# 09_eMMC.net
KiCad netlist of a schematic drawn in Altium Designer
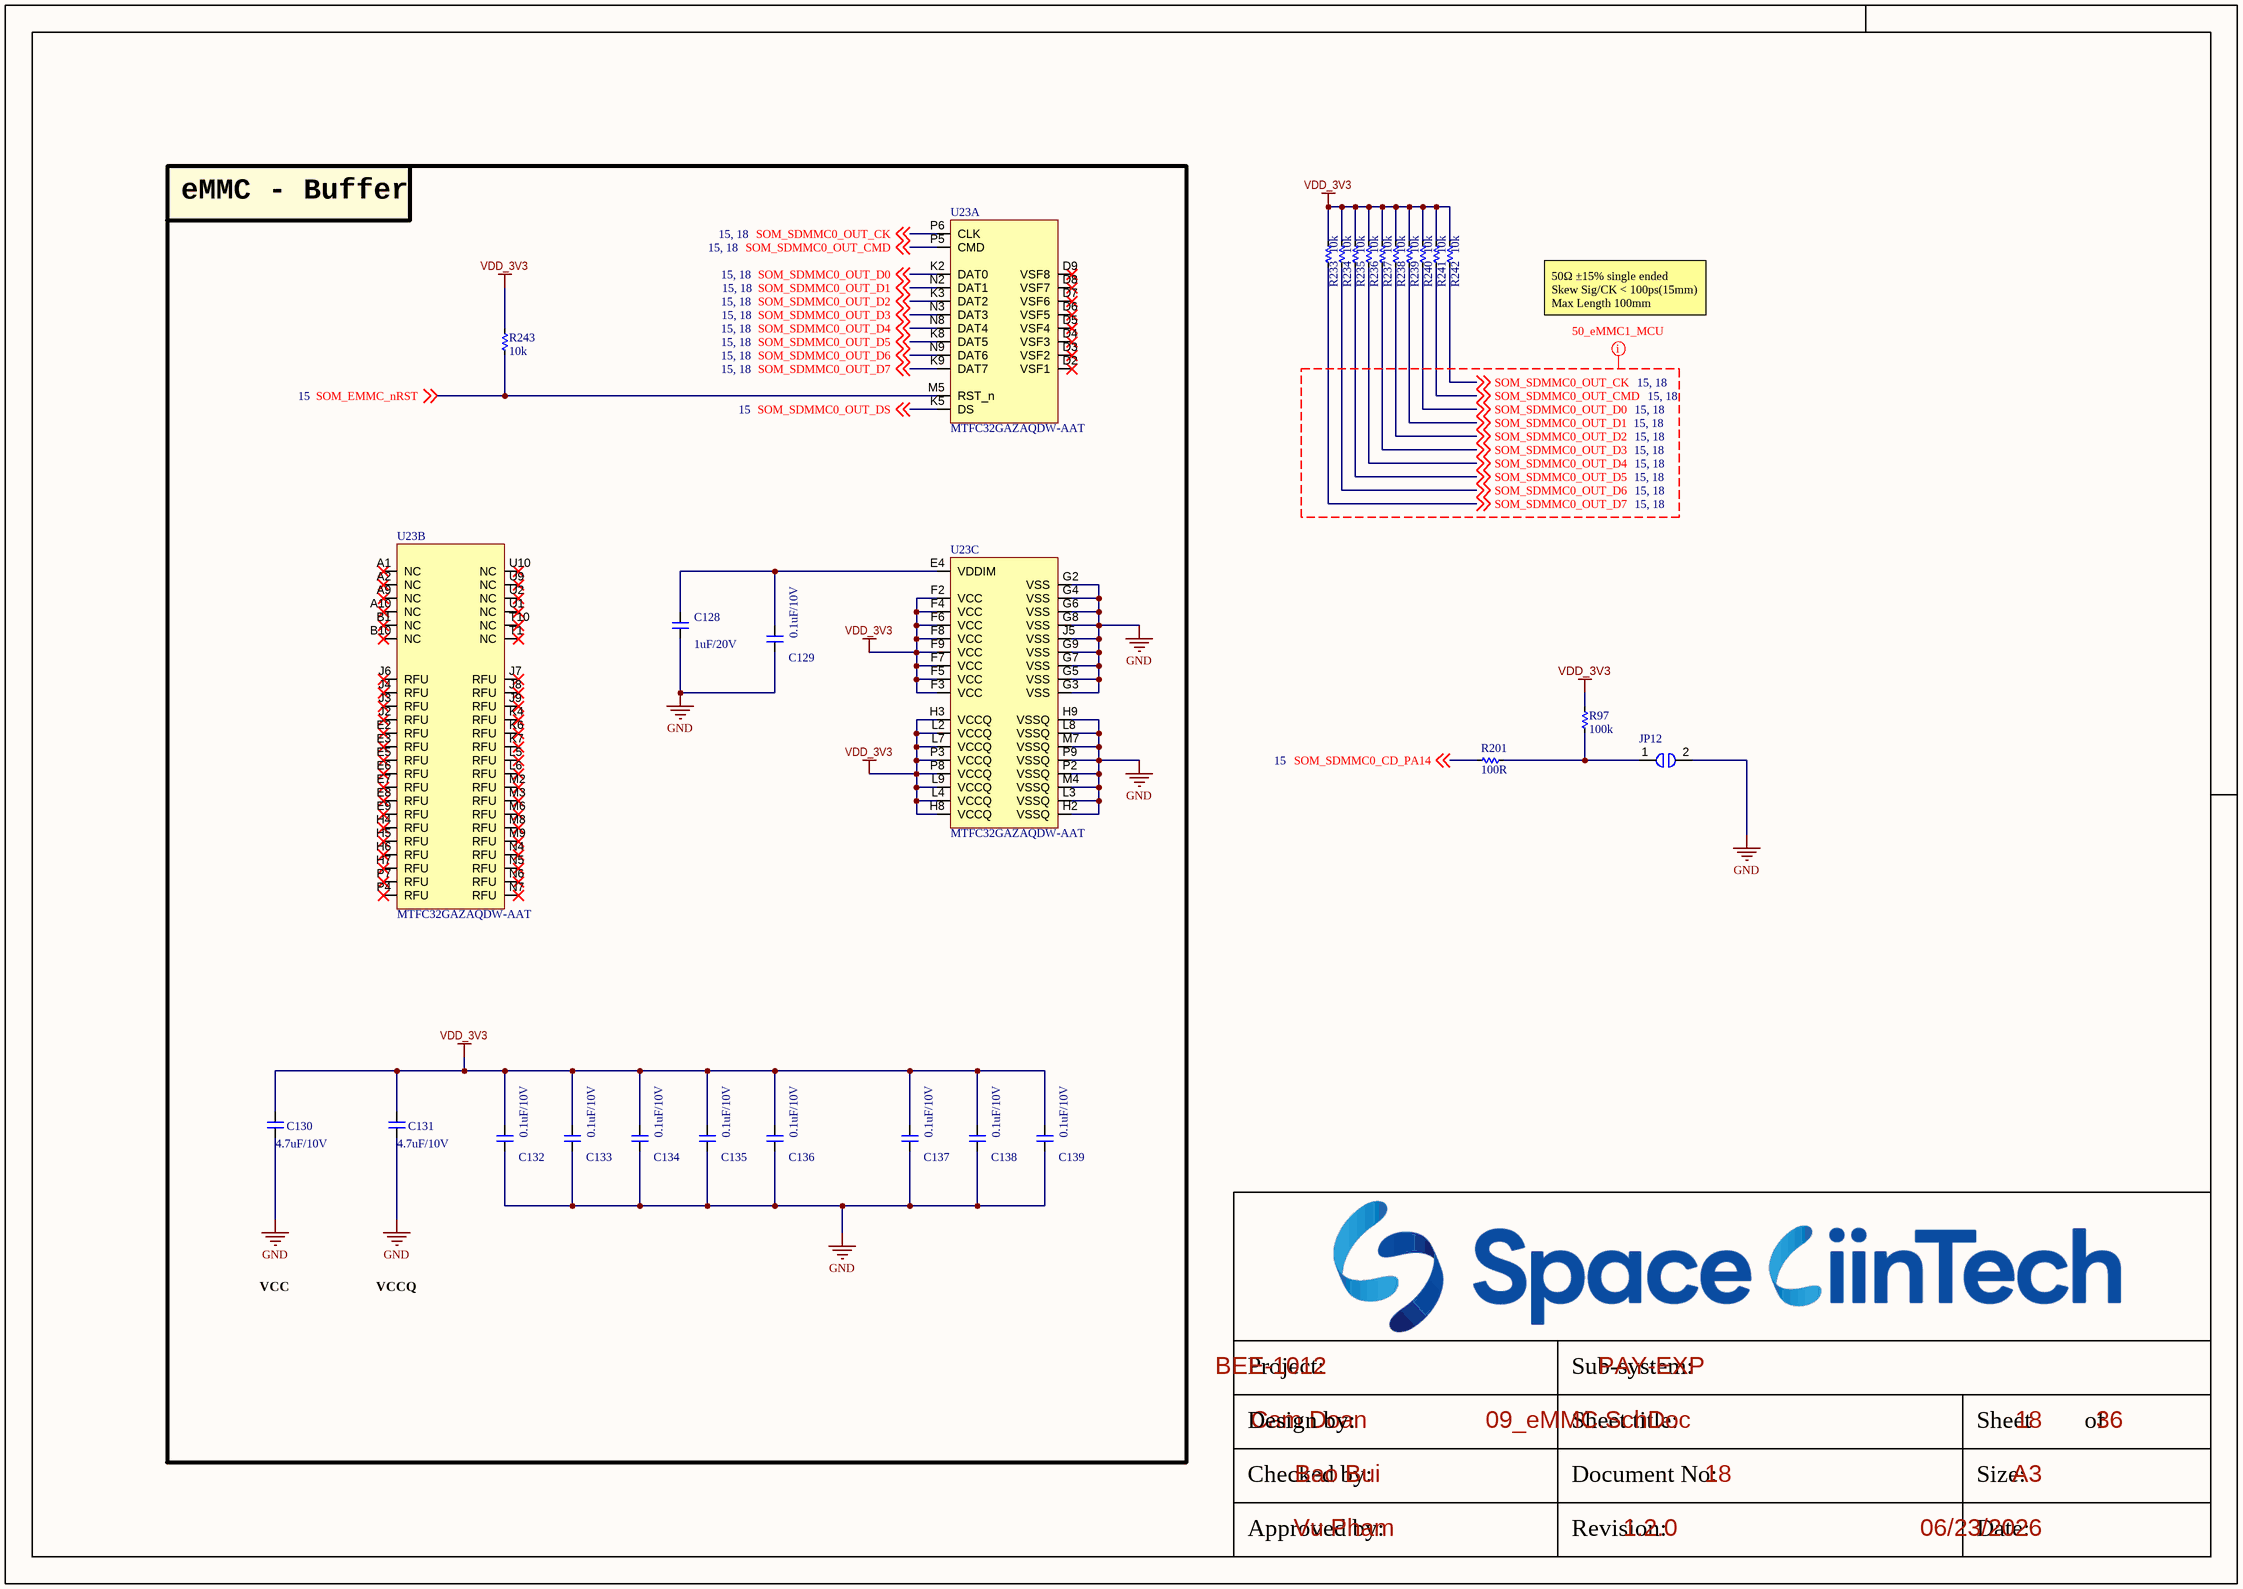
[diagram p0: 09_eMMC.SchDoc]

(export (version "E")
  (design (tool "Eeschema 10.0.6"))
  (components
    (comp (ref "C128")
      (value "1uF/20V")
      (footprint "CAP_C_1005X60")
      (description "CAP")
      (libsource (lib "LABLIB") (part "_CAP_C_2"))
    )
    (comp (ref "C129")
      (value "0.1uF/10V")
      (footprint "CAP_C_1005X60")
      (description "CAP")
      (libsource (lib "LABLIB") (part "_CAP_C_2"))
    )
    (comp (ref "C130")
      (value "4.7uF/10V")
      (footprint "CAP_C_1005X60")
      (description "CAP")
      (libsource (lib "LABLIB") (part "_CAP_C_2"))
    )
    (comp (ref "C131")
      (value "4.7uF/10V")
      (footprint "CAP_C_1005X60")
      (description "CAP")
      (libsource (lib "LABLIB") (part "_CAP_C_2"))
    )
    (comp (ref "C132")
      (value "0.1uF/10V")
      (footprint "CAP_C_1005X60")
      (description "CAP")
      (libsource (lib "LABLIB") (part "_CAP_C_2"))
    )
    (comp (ref "C133")
      (value "0.1uF/10V")
      (footprint "CAP_C_1005X60")
      (description "CAP")
      (libsource (lib "LABLIB") (part "_CAP_C_2"))
    )
    (comp (ref "C134")
      (value "0.1uF/10V")
      (footprint "CAP_C_1005X60")
      (description "CAP")
      (libsource (lib "LABLIB") (part "_CAP_C_2"))
    )
    (comp (ref "C135")
      (value "0.1uF/10V")
      (footprint "CAP_C_1005X60")
      (description "CAP")
      (libsource (lib "LABLIB") (part "_CAP_C_2"))
    )
    (comp (ref "C136")
      (value "0.1uF/10V")
      (footprint "CAP_C_1005X60")
      (description "CAP")
      (libsource (lib "LABLIB") (part "_CAP_C_2"))
    )
    (comp (ref "C137")
      (value "0.1uF/10V")
      (footprint "CAP_C_1005X60")
      (description "CAP")
      (libsource (lib "LABLIB") (part "_CAP_C_2"))
    )
    (comp (ref "C138")
      (value "0.1uF/10V")
      (footprint "CAP_C_1005X60")
      (description "CAP")
      (libsource (lib "LABLIB") (part "_CAP_C_2"))
    )
    (comp (ref "C139")
      (value "0.1uF/10V")
      (footprint "CAP_C_1005X60")
      (description "CAP")
      (libsource (lib "LABLIB") (part "_CAP_C_2"))
    )
    (comp (ref "JP12")
      (value "~")
      (footprint "TESTPOINT_SHORT_120X100_60")
      (libsource (lib "LABLIB") (part "JUMPER_1_1"))
    )
    (comp (ref "R97")
      (value "100k")
      (footprint "RES_C_1005X40")
      (description "RES")
      (libsource (lib "LABLIB") (part "_RES_B_2"))
    )
    (comp (ref "R201")
      (value "100R")
      (footprint "RES_C_1005X40")
      (description "RES")
      (libsource (lib "LABLIB") (part "_RES_B_2"))
    )
    (comp (ref "R233")
      (value "10k")
      (footprint "RES_C_1005X40")
      (description "RES")
      (libsource (lib "LABLIB") (part "_RES_B_2"))
    )
    (comp (ref "R234")
      (value "10k")
      (footprint "RES_C_1005X40")
      (description "RES")
      (libsource (lib "LABLIB") (part "_RES_B_2"))
    )
    (comp (ref "R235")
      (value "10k")
      (footprint "RES_C_1005X40")
      (description "RES")
      (libsource (lib "LABLIB") (part "_RES_B_2"))
    )
    (comp (ref "R236")
      (value "10k")
      (footprint "RES_C_1005X40")
      (description "RES")
      (libsource (lib "LABLIB") (part "_RES_B_2"))
    )
    (comp (ref "R237")
      (value "10k")
      (footprint "RES_C_1005X40")
      (description "RES")
      (libsource (lib "LABLIB") (part "_RES_B_2"))
    )
    (comp (ref "R238")
      (value "10k")
      (footprint "RES_C_1005X40")
      (description "RES")
      (libsource (lib "LABLIB") (part "_RES_B_2"))
    )
    (comp (ref "R239")
      (value "10k")
      (footprint "RES_C_1005X40")
      (description "RES")
      (libsource (lib "LABLIB") (part "_RES_B_2"))
    )
    (comp (ref "R240")
      (value "10k")
      (footprint "RES_C_1005X40")
      (description "RES")
      (libsource (lib "LABLIB") (part "_RES_B_2"))
    )
    (comp (ref "R241")
      (value "10k")
      (footprint "RES_C_1005X40")
      (description "RES")
      (libsource (lib "LABLIB") (part "_RES_B_2"))
    )
    (comp (ref "R242")
      (value "10k")
      (footprint "RES_C_1005X40")
      (description "RES")
      (libsource (lib "LABLIB") (part "_RES_B_2"))
    )
    (comp (ref "R243")
      (value "10k")
      (footprint "RES_C_1005X40")
      (description "RES")
      (libsource (lib "LABLIB") (part "_RES_B_2"))
    )
    (comp (ref "U23")
      (value "MTFC32GAZAQDW-AAT")
      (footprint "BGA_100_C_100P_10X17_1400X1800X150")
      (libsource (lib "emmc_nofootprint") (part "MTFC32GAZAQDW-AAT"))
    )
  )
  (nets
    (net (code "1") (name "GND") (class "Default")
      (node (ref "C128") (pin "1") (pinfunction "1_1") (pintype "passive"))
      (node (ref "C129") (pin "1") (pinfunction "1_1") (pintype "passive"))
      (node (ref "C130") (pin "1") (pinfunction "1_1") (pintype "passive"))
      (node (ref "C131") (pin "1") (pinfunction "1_1") (pintype "passive"))
      (node (ref "C132") (pin "1") (pinfunction "1_1") (pintype "passive"))
      (node (ref "C133") (pin "1") (pinfunction "1_1") (pintype "passive"))
      (node (ref "C134") (pin "1") (pinfunction "1_1") (pintype "passive"))
      (node (ref "C135") (pin "1") (pinfunction "1_1") (pintype "passive"))
      (node (ref "C136") (pin "1") (pinfunction "1_1") (pintype "passive"))
      (node (ref "C137") (pin "1") (pinfunction "1_1") (pintype "passive"))
      (node (ref "C138") (pin "1") (pinfunction "1_1") (pintype "passive"))
      (node (ref "C139") (pin "1") (pinfunction "1_1") (pintype "passive"))
      (node (ref "JP12") (pin "2") (pinfunction "2_2") (pintype "passive"))
      (node (ref "U23") (pin "G2") (pinfunction "VSS_G2") (pintype "passive"))
      (node (ref "U23") (pin "G3") (pinfunction "VSS_G3") (pintype "passive"))
      (node (ref "U23") (pin "G4") (pinfunction "VSS_G4") (pintype "passive"))
      (node (ref "U23") (pin "G5") (pinfunction "VSS_G5") (pintype "passive"))
      (node (ref "U23") (pin "G6") (pinfunction "VSS_G6") (pintype "passive"))
      (node (ref "U23") (pin "G7") (pinfunction "VSS_G7") (pintype "passive"))
      (node (ref "U23") (pin "G8") (pinfunction "VSS_G8") (pintype "passive"))
      (node (ref "U23") (pin "G9") (pinfunction "VSS_G9") (pintype "passive"))
      (node (ref "U23") (pin "H2") (pinfunction "VSSQ_H2") (pintype "passive"))
      (node (ref "U23") (pin "H9") (pinfunction "VSSQ_H9") (pintype "passive"))
      (node (ref "U23") (pin "J5") (pinfunction "VSS_J5") (pintype "passive"))
      (node (ref "U23") (pin "L3") (pinfunction "VSSQ_L3") (pintype "passive"))
      (node (ref "U23") (pin "L8") (pinfunction "VSSQ_L8") (pintype "passive"))
      (node (ref "U23") (pin "M4") (pinfunction "VSSQ_M4") (pintype "passive"))
      (node (ref "U23") (pin "M7") (pinfunction "VSSQ_M7") (pintype "passive"))
      (node (ref "U23") (pin "P2") (pinfunction "VSSQ_P2") (pintype "passive"))
      (node (ref "U23") (pin "P9") (pinfunction "VSSQ_P9") (pintype "passive"))
    )
    (net (code "2") (name "Net-(JP12-Pad1)") (class "Default")
      (node (ref "JP12") (pin "1") (pinfunction "1_1") (pintype "passive"))
      (node (ref "R201") (pin "2") (pinfunction "2_2") (pintype "passive"))
      (node (ref "R97") (pin "1") (pinfunction "1_1") (pintype "passive"))
    )
    (net (code "3") (name "Net-(U23C-VDDIM)") (class "Default")
      (node (ref "C128") (pin "2") (pinfunction "2_2") (pintype "passive"))
      (node (ref "C129") (pin "2") (pinfunction "2_2") (pintype "passive"))
      (node (ref "U23") (pin "E4") (pinfunction "VDDIM_E4") (pintype "passive"))
    )
    (net (code "4") (name "SOM_EMMC_nRST") (class "Default")
      (node (ref "R243") (pin "1") (pinfunction "1_1") (pintype "passive"))
      (node (ref "U23") (pin "M5") (pinfunction "RST_n_M5") (pintype "passive"))
    )
    (net (code "5") (name "SOM_SDMMC0_CD_PA14") (class "Default")
      (node (ref "R201") (pin "1") (pinfunction "1_1") (pintype "passive"))
    )
    (net (code "6") (name "SOM_SDMMC0_OUT_CK") (class "Default")
      (node (ref "R242") (pin "1") (pinfunction "1_1") (pintype "passive"))
      (node (ref "U23") (pin "P6") (pinfunction "CLK_P6") (pintype "passive"))
    )
    (net (code "7") (name "SOM_SDMMC0_OUT_CMD") (class "Default")
      (node (ref "R241") (pin "1") (pinfunction "1_1") (pintype "passive"))
      (node (ref "U23") (pin "P5") (pinfunction "CMD_P5") (pintype "passive"))
    )
    (net (code "8") (name "SOM_SDMMC0_OUT_D0") (class "Default")
      (node (ref "R240") (pin "1") (pinfunction "1_1") (pintype "passive"))
      (node (ref "U23") (pin "K2") (pinfunction "DAT0_K2") (pintype "passive"))
    )
    (net (code "9") (name "SOM_SDMMC0_OUT_D1") (class "Default")
      (node (ref "R239") (pin "1") (pinfunction "1_1") (pintype "passive"))
      (node (ref "U23") (pin "N2") (pinfunction "DAT1_N2") (pintype "passive"))
    )
    (net (code "10") (name "SOM_SDMMC0_OUT_D2") (class "Default")
      (node (ref "R238") (pin "1") (pinfunction "1_1") (pintype "passive"))
      (node (ref "U23") (pin "K3") (pinfunction "DAT2_K3") (pintype "passive"))
    )
    (net (code "11") (name "SOM_SDMMC0_OUT_D3") (class "Default")
      (node (ref "R237") (pin "1") (pinfunction "1_1") (pintype "passive"))
      (node (ref "U23") (pin "N3") (pinfunction "DAT3_N3") (pintype "passive"))
    )
    (net (code "12") (name "SOM_SDMMC0_OUT_D4") (class "Default")
      (node (ref "R236") (pin "1") (pinfunction "1_1") (pintype "passive"))
      (node (ref "U23") (pin "N8") (pinfunction "DAT4_N8") (pintype "passive"))
    )
    (net (code "13") (name "SOM_SDMMC0_OUT_D5") (class "Default")
      (node (ref "R235") (pin "1") (pinfunction "1_1") (pintype "passive"))
      (node (ref "U23") (pin "K8") (pinfunction "DAT5_K8") (pintype "passive"))
    )
    (net (code "14") (name "SOM_SDMMC0_OUT_D6") (class "Default")
      (node (ref "R234") (pin "1") (pinfunction "1_1") (pintype "passive"))
      (node (ref "U23") (pin "N9") (pinfunction "DAT6_N9") (pintype "passive"))
    )
    (net (code "15") (name "SOM_SDMMC0_OUT_D7") (class "Default")
      (node (ref "R233") (pin "1") (pinfunction "1_1") (pintype "passive"))
      (node (ref "U23") (pin "K9") (pinfunction "DAT7_K9") (pintype "passive"))
    )
    (net (code "16") (name "SOM_SDMMC0_OUT_DS") (class "Default")
      (node (ref "U23") (pin "K5") (pinfunction "DS_K5") (pintype "passive"))
    )
    (net (code "17") (name "VDD_3V3") (class "Default")
      (node (ref "C130") (pin "2") (pinfunction "2_2") (pintype "passive"))
      (node (ref "C131") (pin "2") (pinfunction "2_2") (pintype "passive"))
      (node (ref "C132") (pin "2") (pinfunction "2_2") (pintype "passive"))
      (node (ref "C133") (pin "2") (pinfunction "2_2") (pintype "passive"))
      (node (ref "C134") (pin "2") (pinfunction "2_2") (pintype "passive"))
      (node (ref "C135") (pin "2") (pinfunction "2_2") (pintype "passive"))
      (node (ref "C136") (pin "2") (pinfunction "2_2") (pintype "passive"))
      (node (ref "C137") (pin "2") (pinfunction "2_2") (pintype "passive"))
      (node (ref "C138") (pin "2") (pinfunction "2_2") (pintype "passive"))
      (node (ref "C139") (pin "2") (pinfunction "2_2") (pintype "passive"))
      (node (ref "R233") (pin "2") (pinfunction "2_2") (pintype "passive"))
      (node (ref "R234") (pin "2") (pinfunction "2_2") (pintype "passive"))
      (node (ref "R235") (pin "2") (pinfunction "2_2") (pintype "passive"))
      (node (ref "R236") (pin "2") (pinfunction "2_2") (pintype "passive"))
      (node (ref "R237") (pin "2") (pinfunction "2_2") (pintype "passive"))
      (node (ref "R238") (pin "2") (pinfunction "2_2") (pintype "passive"))
      (node (ref "R239") (pin "2") (pinfunction "2_2") (pintype "passive"))
      (node (ref "R240") (pin "2") (pinfunction "2_2") (pintype "passive"))
      (node (ref "R241") (pin "2") (pinfunction "2_2") (pintype "passive"))
      (node (ref "R242") (pin "2") (pinfunction "2_2") (pintype "passive"))
      (node (ref "R243") (pin "2") (pinfunction "2_2") (pintype "passive"))
      (node (ref "R97") (pin "2") (pinfunction "2_2") (pintype "passive"))
      (node (ref "U23") (pin "F2") (pinfunction "VCC_F2") (pintype "passive"))
      (node (ref "U23") (pin "F3") (pinfunction "VCC_F3") (pintype "passive"))
      (node (ref "U23") (pin "F4") (pinfunction "VCC_F4") (pintype "passive"))
      (node (ref "U23") (pin "F5") (pinfunction "VCC_F5") (pintype "passive"))
      (node (ref "U23") (pin "F6") (pinfunction "VCC_F6") (pintype "passive"))
      (node (ref "U23") (pin "F7") (pinfunction "VCC_F7") (pintype "passive"))
      (node (ref "U23") (pin "F8") (pinfunction "VCC_F8") (pintype "passive"))
      (node (ref "U23") (pin "F9") (pinfunction "VCC_F9") (pintype "passive"))
      (node (ref "U23") (pin "H3") (pinfunction "VCCQ_H3") (pintype "passive"))
      (node (ref "U23") (pin "H8") (pinfunction "VCCQ_H8") (pintype "passive"))
      (node (ref "U23") (pin "L2") (pinfunction "VCCQ_L2") (pintype "passive"))
      (node (ref "U23") (pin "L4") (pinfunction "VCCQ_L4") (pintype "passive"))
      (node (ref "U23") (pin "L7") (pinfunction "VCCQ_L7") (pintype "passive"))
      (node (ref "U23") (pin "L9") (pinfunction "VCCQ_L9") (pintype "passive"))
      (node (ref "U23") (pin "P3") (pinfunction "VCCQ_P3") (pintype "passive"))
      (node (ref "U23") (pin "P8") (pinfunction "VCCQ_P8") (pintype "passive"))
    )
    (net (code "18") (name "unconnected-(U23A-VSF1-PadD2)") (class "Default")
      (node (ref "U23") (pin "D2") (pinfunction "VSF1_D2") (pintype "passive+no_connect"))
    )
    (net (code "19") (name "unconnected-(U23A-VSF2-PadD3)") (class "Default")
      (node (ref "U23") (pin "D3") (pinfunction "VSF2_D3") (pintype "passive+no_connect"))
    )
    (net (code "20") (name "unconnected-(U23A-VSF3-PadD4)") (class "Default")
      (node (ref "U23") (pin "D4") (pinfunction "VSF3_D4") (pintype "passive+no_connect"))
    )
    (net (code "21") (name "unconnected-(U23A-VSF4-PadD5)") (class "Default")
      (node (ref "U23") (pin "D5") (pinfunction "VSF4_D5") (pintype "passive+no_connect"))
    )
    (net (code "22") (name "unconnected-(U23A-VSF5-PadD6)") (class "Default")
      (node (ref "U23") (pin "D6") (pinfunction "VSF5_D6") (pintype "passive+no_connect"))
    )
    (net (code "23") (name "unconnected-(U23A-VSF6-PadD7)") (class "Default")
      (node (ref "U23") (pin "D7") (pinfunction "VSF6_D7") (pintype "passive+no_connect"))
    )
    (net (code "24") (name "unconnected-(U23A-VSF7-PadD8)") (class "Default")
      (node (ref "U23") (pin "D8") (pinfunction "VSF7_D8") (pintype "passive+no_connect"))
    )
    (net (code "25") (name "unconnected-(U23A-VSF8-PadD9)") (class "Default")
      (node (ref "U23") (pin "D9") (pinfunction "VSF8_D9") (pintype "passive+no_connect"))
    )
    (net (code "26") (name "unconnected-(U23B-NC-PadA1)") (class "Default")
      (node (ref "U23") (pin "A1") (pinfunction "NC_A1") (pintype "passive+no_connect"))
    )
    (net (code "27") (name "unconnected-(U23B-NC-PadA2)") (class "Default")
      (node (ref "U23") (pin "A2") (pinfunction "NC_A2") (pintype "passive+no_connect"))
    )
    (net (code "28") (name "unconnected-(U23B-NC-PadA9)") (class "Default")
      (node (ref "U23") (pin "A9") (pinfunction "NC_A9") (pintype "passive+no_connect"))
    )
    (net (code "29") (name "unconnected-(U23B-NC-PadA10)") (class "Default")
      (node (ref "U23") (pin "A10") (pinfunction "NC_A10") (pintype "passive+no_connect"))
    )
    (net (code "30") (name "unconnected-(U23B-NC-PadB1)") (class "Default")
      (node (ref "U23") (pin "B1") (pinfunction "NC_B1") (pintype "passive+no_connect"))
    )
    (net (code "31") (name "unconnected-(U23B-NC-PadB10)") (class "Default")
      (node (ref "U23") (pin "B10") (pinfunction "NC_B10") (pintype "passive+no_connect"))
    )
    (net (code "32") (name "unconnected-(U23B-NC-PadT1)") (class "Default")
      (node (ref "U23") (pin "T1") (pinfunction "NC_T1") (pintype "passive+no_connect"))
    )
    (net (code "33") (name "unconnected-(U23B-NC-PadT10)") (class "Default")
      (node (ref "U23") (pin "T10") (pinfunction "NC_T10") (pintype "passive+no_connect"))
    )
    (net (code "34") (name "unconnected-(U23B-NC-PadU1)") (class "Default")
      (node (ref "U23") (pin "U1") (pinfunction "NC_U1") (pintype "passive+no_connect"))
    )
    (net (code "35") (name "unconnected-(U23B-NC-PadU2)") (class "Default")
      (node (ref "U23") (pin "U2") (pinfunction "NC_U2") (pintype "passive+no_connect"))
    )
    (net (code "36") (name "unconnected-(U23B-NC-PadU9)") (class "Default")
      (node (ref "U23") (pin "U9") (pinfunction "NC_U9") (pintype "passive+no_connect"))
    )
    (net (code "37") (name "unconnected-(U23B-NC-PadU10)") (class "Default")
      (node (ref "U23") (pin "U10") (pinfunction "NC_U10") (pintype "passive+no_connect"))
    )
    (net (code "38") (name "unconnected-(U23B-RFU-PadE2)") (class "Default")
      (node (ref "U23") (pin "E2") (pinfunction "RFU_E2") (pintype "passive+no_connect"))
    )
    (net (code "39") (name "unconnected-(U23B-RFU-PadE3)") (class "Default")
      (node (ref "U23") (pin "E3") (pinfunction "RFU_E3") (pintype "passive+no_connect"))
    )
    (net (code "40") (name "unconnected-(U23B-RFU-PadE5)") (class "Default")
      (node (ref "U23") (pin "E5") (pinfunction "RFU_E5") (pintype "passive+no_connect"))
    )
    (net (code "41") (name "unconnected-(U23B-RFU-PadE6)") (class "Default")
      (node (ref "U23") (pin "E6") (pinfunction "RFU_E6") (pintype "passive+no_connect"))
    )
    (net (code "42") (name "unconnected-(U23B-RFU-PadE7)") (class "Default")
      (node (ref "U23") (pin "E7") (pinfunction "RFU_E7") (pintype "passive+no_connect"))
    )
    (net (code "43") (name "unconnected-(U23B-RFU-PadE8)") (class "Default")
      (node (ref "U23") (pin "E8") (pinfunction "RFU_E8") (pintype "passive+no_connect"))
    )
    (net (code "44") (name "unconnected-(U23B-RFU-PadE9)") (class "Default")
      (node (ref "U23") (pin "E9") (pinfunction "RFU_E9") (pintype "passive+no_connect"))
    )
    (net (code "45") (name "unconnected-(U23B-RFU-PadH4)") (class "Default")
      (node (ref "U23") (pin "H4") (pinfunction "RFU_H4") (pintype "passive+no_connect"))
    )
    (net (code "46") (name "unconnected-(U23B-RFU-PadH5)") (class "Default")
      (node (ref "U23") (pin "H5") (pinfunction "RFU_H5") (pintype "passive+no_connect"))
    )
    (net (code "47") (name "unconnected-(U23B-RFU-PadH6)") (class "Default")
      (node (ref "U23") (pin "H6") (pinfunction "RFU_H6") (pintype "passive+no_connect"))
    )
    (net (code "48") (name "unconnected-(U23B-RFU-PadH7)") (class "Default")
      (node (ref "U23") (pin "H7") (pinfunction "RFU_H7") (pintype "passive+no_connect"))
    )
    (net (code "49") (name "unconnected-(U23B-RFU-PadJ2)") (class "Default")
      (node (ref "U23") (pin "J2") (pinfunction "RFU_J2") (pintype "passive+no_connect"))
    )
    (net (code "50") (name "unconnected-(U23B-RFU-PadJ3)") (class "Default")
      (node (ref "U23") (pin "J3") (pinfunction "RFU_J3") (pintype "passive+no_connect"))
    )
    (net (code "51") (name "unconnected-(U23B-RFU-PadJ4)") (class "Default")
      (node (ref "U23") (pin "J4") (pinfunction "RFU_J4") (pintype "passive+no_connect"))
    )
    (net (code "52") (name "unconnected-(U23B-RFU-PadJ6)") (class "Default")
      (node (ref "U23") (pin "J6") (pinfunction "RFU_J6") (pintype "passive+no_connect"))
    )
    (net (code "53") (name "unconnected-(U23B-RFU-PadJ7)") (class "Default")
      (node (ref "U23") (pin "J7") (pinfunction "RFU_J7") (pintype "passive+no_connect"))
    )
    (net (code "54") (name "unconnected-(U23B-RFU-PadJ8)") (class "Default")
      (node (ref "U23") (pin "J8") (pinfunction "RFU_J8") (pintype "passive+no_connect"))
    )
    (net (code "55") (name "unconnected-(U23B-RFU-PadJ9)") (class "Default")
      (node (ref "U23") (pin "J9") (pinfunction "RFU_J9") (pintype "passive+no_connect"))
    )
    (net (code "56") (name "unconnected-(U23B-RFU-PadK4)") (class "Default")
      (node (ref "U23") (pin "K4") (pinfunction "RFU_K4") (pintype "passive+no_connect"))
    )
    (net (code "57") (name "unconnected-(U23B-RFU-PadK6)") (class "Default")
      (node (ref "U23") (pin "K6") (pinfunction "RFU_K6") (pintype "passive+no_connect"))
    )
    (net (code "58") (name "unconnected-(U23B-RFU-PadK7)") (class "Default")
      (node (ref "U23") (pin "K7") (pinfunction "RFU_K7") (pintype "passive+no_connect"))
    )
    (net (code "59") (name "unconnected-(U23B-RFU-PadL5)") (class "Default")
      (node (ref "U23") (pin "L5") (pinfunction "RFU_L5") (pintype "passive+no_connect"))
    )
    (net (code "60") (name "unconnected-(U23B-RFU-PadL6)") (class "Default")
      (node (ref "U23") (pin "L6") (pinfunction "RFU_L6") (pintype "passive+no_connect"))
    )
    (net (code "61") (name "unconnected-(U23B-RFU-PadM2)") (class "Default")
      (node (ref "U23") (pin "M2") (pinfunction "RFU_M2") (pintype "passive+no_connect"))
    )
    (net (code "62") (name "unconnected-(U23B-RFU-PadM3)") (class "Default")
      (node (ref "U23") (pin "M3") (pinfunction "RFU_M3") (pintype "passive+no_connect"))
    )
    (net (code "63") (name "unconnected-(U23B-RFU-PadM6)") (class "Default")
      (node (ref "U23") (pin "M6") (pinfunction "RFU_M6") (pintype "passive+no_connect"))
    )
    (net (code "64") (name "unconnected-(U23B-RFU-PadM8)") (class "Default")
      (node (ref "U23") (pin "M8") (pinfunction "RFU_M8") (pintype "passive+no_connect"))
    )
    (net (code "65") (name "unconnected-(U23B-RFU-PadM9)") (class "Default")
      (node (ref "U23") (pin "M9") (pinfunction "RFU_M9") (pintype "passive+no_connect"))
    )
    (net (code "66") (name "unconnected-(U23B-RFU-PadN4)") (class "Default")
      (node (ref "U23") (pin "N4") (pinfunction "RFU_N4") (pintype "passive+no_connect"))
    )
    (net (code "67") (name "unconnected-(U23B-RFU-PadN5)") (class "Default")
      (node (ref "U23") (pin "N5") (pinfunction "RFU_N5") (pintype "passive+no_connect"))
    )
    (net (code "68") (name "unconnected-(U23B-RFU-PadN6)") (class "Default")
      (node (ref "U23") (pin "N6") (pinfunction "RFU_N6") (pintype "passive+no_connect"))
    )
    (net (code "69") (name "unconnected-(U23B-RFU-PadN7)") (class "Default")
      (node (ref "U23") (pin "N7") (pinfunction "RFU_N7") (pintype "passive+no_connect"))
    )
    (net (code "70") (name "unconnected-(U23B-RFU-PadP4)") (class "Default")
      (node (ref "U23") (pin "P4") (pinfunction "RFU_P4") (pintype "passive+no_connect"))
    )
    (net (code "71") (name "unconnected-(U23B-RFU-PadP7)") (class "Default")
      (node (ref "U23") (pin "P7") (pinfunction "RFU_P7") (pintype "passive+no_connect"))
    )
  )
)
